# Sheet2.net
KiCad netlist of a schematic drawn in Altium Designer
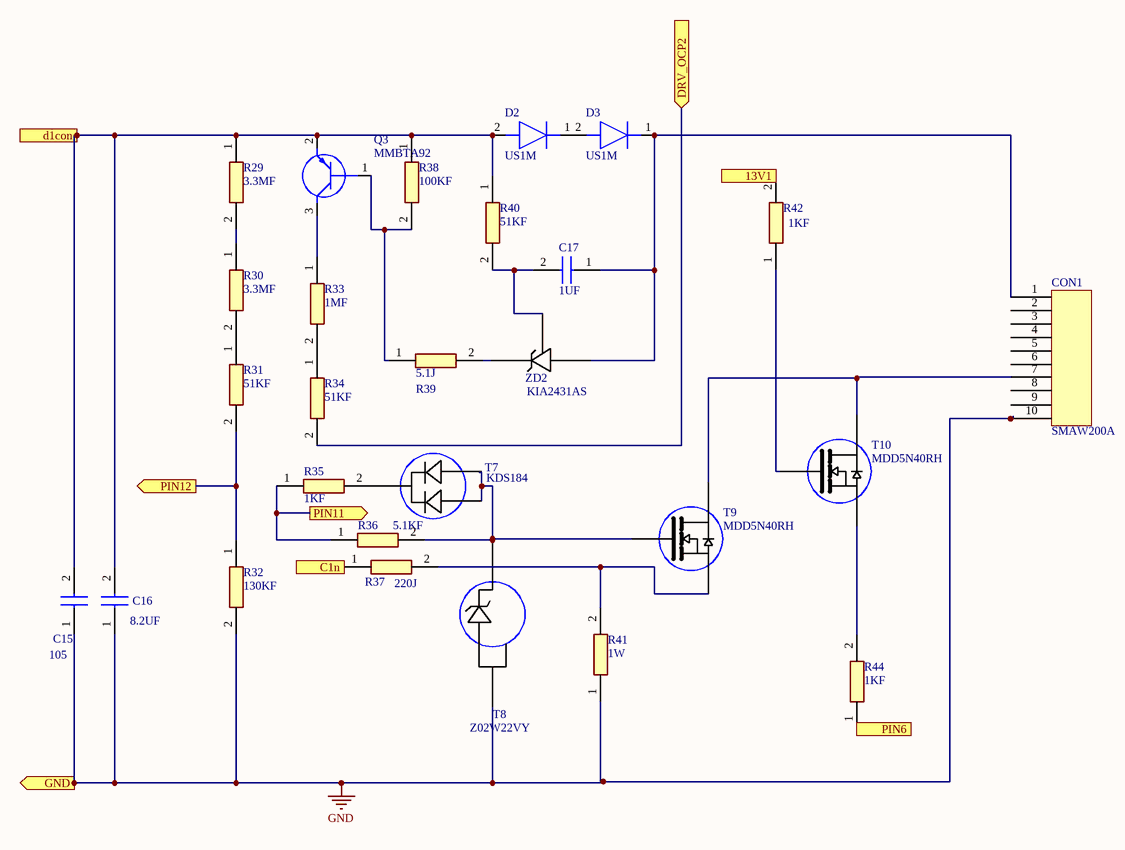
[diagram p0: Sheet2.SchDoc]

(export (version "E")
  (design (tool "Eeschema 10.0.6"))
  (components
    (comp (ref "C15")
      (value "105")
      (footprint "SamacSys:CAPPRD200W55D525H1200")
      (description "Capacitor")
      (fields
        (field (name "MANUFACTURER_PART_NUMBER") "ECA-1HM0R1")
        (field (name "MOUSER PART NUMBER") "667-ECA-1HM0R1")
      )
      (libsource (lib "*") (part "ECA-1HM0R1"))
    )
    (comp (ref "C16")
      (value "8.2UF")
      (footprint "SamacSys:CAPPRD200W55D525H1200")
      (description "Capacitor")
      (fields
        (field (name "MANUFACTURER_PART_NUMBER") "ECA-1HM0R1")
        (field (name "MOUSER PART NUMBER") "667-ECA-1HM0R1")
      )
      (libsource (lib "*") (part "ECA-1HM0R1"))
    )
    (comp (ref "C17")
      (value "1UF")
      (footprint "SamacSys:CAPPRD200W55D525H1200")
      (description "Capacitor")
      (fields
        (field (name "MANUFACTURER_PART_NUMBER") "ECA-1HM0R1")
        (field (name "MOUSER PART NUMBER") "667-ECA-1HM0R1")
      )
      (libsource (lib "*") (part "ECA-1HM0R1"))
    )
    (comp (ref "CON1")
      (value "SMAW200A")
      (footprint "SMAW200A")
      (libsource (lib "SMAW200A") (part "SMAW200A"))
    )
    (comp (ref "D2")
      (value "US1M")
      (footprint "SamacSys:DIOM5127X229N")
      (description "Diode")
      (fields
        (field (name "MANUFACTURER_PART_NUMBER") "US1M-E3/61T")
        (field (name "MOUSER PART NUMBER") "625-US1M-E3")
      )
      (libsource (lib "*") (part "US1M-E3_61T"))
    )
    (comp (ref "D3")
      (value "US1M")
      (footprint "SamacSys:DIOM5127X229N")
      (description "Diode")
      (fields
        (field (name "MANUFACTURER_PART_NUMBER") "US1M-E3/61T")
        (field (name "MOUSER PART NUMBER") "625-US1M-E3")
      )
      (libsource (lib "*") (part "US1M-E3_61T"))
    )
    (comp (ref "Q3")
      (value "MMBTA92")
      (footprint "SamacSys:SOT95P245X130-3N")
      (description "Transistor BJT PNP")
      (libsource (lib "*") (part "MMBTA92"))
    )
    (comp (ref "R29")
      (value "3.3MF")
      (footprint "SamacSys:RESAD1170W45L370D200")
      (description "Resistor")
      (fields
        (field (name "MANUFACTURER_PART_NUMBER") "MFR3-10KFC")
        (field (name "MOUSER PART NUMBER") "756-MFR3-10KFC")
      )
      (libsource (lib "*") (part "MFR3-10KFC"))
    )
    (comp (ref "R30")
      (value "3.3MF")
      (footprint "SamacSys:RESAD1170W45L370D200")
      (description "Resistor")
      (fields
        (field (name "MANUFACTURER_PART_NUMBER") "MFR3-10KFC")
        (field (name "MOUSER PART NUMBER") "756-MFR3-10KFC")
      )
      (libsource (lib "*") (part "MFR3-10KFC"))
    )
    (comp (ref "R31")
      (value "51KF")
      (footprint "SamacSys:RESAD1170W45L370D200")
      (description "Resistor")
      (fields
        (field (name "MANUFACTURER_PART_NUMBER") "MFR3-10KFC")
        (field (name "MOUSER PART NUMBER") "756-MFR3-10KFC")
      )
      (libsource (lib "*") (part "MFR3-10KFC"))
    )
    (comp (ref "R32")
      (value "130KF")
      (footprint "SamacSys:RESAD1170W45L370D200")
      (description "Resistor")
      (fields
        (field (name "MANUFACTURER_PART_NUMBER") "MFR3-10KFC")
        (field (name "MOUSER PART NUMBER") "756-MFR3-10KFC")
      )
      (libsource (lib "*") (part "MFR3-10KFC"))
    )
    (comp (ref "R33")
      (value "1MF")
      (footprint "SamacSys:RESAD1170W45L370D200")
      (description "Resistor")
      (fields
        (field (name "MANUFACTURER_PART_NUMBER") "MFR3-10KFC")
        (field (name "MOUSER PART NUMBER") "756-MFR3-10KFC")
      )
      (libsource (lib "*") (part "MFR3-10KFC"))
    )
    (comp (ref "R34")
      (value "51KF")
      (footprint "SamacSys:RESAD1170W45L370D200")
      (description "Resistor")
      (fields
        (field (name "MANUFACTURER_PART_NUMBER") "MFR3-10KFC")
        (field (name "MOUSER PART NUMBER") "756-MFR3-10KFC")
      )
      (libsource (lib "*") (part "MFR3-10KFC"))
    )
    (comp (ref "R35")
      (value "1KF")
      (footprint "SamacSys:RESAD1170W45L370D200")
      (description "Resistor")
      (fields
        (field (name "MANUFACTURER_PART_NUMBER") "MFR3-10KFC")
        (field (name "MOUSER PART NUMBER") "756-MFR3-10KFC")
      )
      (libsource (lib "") (part "MFR3-10KFC_1"))
    )
    (comp (ref "R36")
      (value "5.1KF")
      (footprint "SamacSys:RESAD1170W45L370D200")
      (description "Resistor")
      (fields
        (field (name "MANUFACTURER_PART_NUMBER") "MFR3-10KFC")
        (field (name "MOUSER PART NUMBER") "756-MFR3-10KFC")
      )
      (libsource (lib "") (part "MFR3-10KFC_1"))
    )
    (comp (ref "R37")
      (value "220J")
      (footprint "SamacSys:RESAD1170W45L370D200")
      (description "Resistor")
      (fields
        (field (name "MANUFACTURER_PART_NUMBER") "MFR3-10KFC")
        (field (name "MOUSER PART NUMBER") "756-MFR3-10KFC")
      )
      (libsource (lib "") (part "MFR3-10KFC_1"))
    )
    (comp (ref "R38")
      (value "100KF")
      (footprint "SamacSys:RESAD1170W45L370D200")
      (description "Resistor")
      (fields
        (field (name "MANUFACTURER_PART_NUMBER") "MFR3-10KFC")
        (field (name "MOUSER PART NUMBER") "756-MFR3-10KFC")
      )
      (libsource (lib "*") (part "MFR3-10KFC"))
    )
    (comp (ref "R39")
      (value "5.1J")
      (footprint "SamacSys:RESAD1170W45L370D200")
      (description "Resistor")
      (fields
        (field (name "MANUFACTURER_PART_NUMBER") "MFR3-10KFC")
        (field (name "MOUSER PART NUMBER") "756-MFR3-10KFC")
      )
      (libsource (lib "") (part "MFR3-10KFC_1"))
    )
    (comp (ref "R40")
      (value "51KF")
      (footprint "SamacSys:RESAD1170W45L370D200")
      (description "Resistor")
      (fields
        (field (name "MANUFACTURER_PART_NUMBER") "MFR3-10KFC")
        (field (name "MOUSER PART NUMBER") "756-MFR3-10KFC")
      )
      (libsource (lib "*") (part "MFR3-10KFC"))
    )
    (comp (ref "R41")
      (value "1W")
      (footprint "SamacSys:RESAD1170W45L370D200")
      (description "Resistor")
      (fields
        (field (name "MANUFACTURER_PART_NUMBER") "MFR3-10KFC")
        (field (name "MOUSER PART NUMBER") "756-MFR3-10KFC")
      )
      (libsource (lib "") (part "MFR3-10KFC_2"))
    )
    (comp (ref "R42")
      (value "1KF")
      (footprint "SamacSys:RESAD1170W45L370D200")
      (description "Resistor")
      (fields
        (field (name "MANUFACTURER_PART_NUMBER") "MFR3-10KFC")
        (field (name "MOUSER PART NUMBER") "756-MFR3-10KFC")
      )
      (libsource (lib "") (part "MFR3-10KFC_2"))
    )
    (comp (ref "R44")
      (value "1KF")
      (footprint "SamacSys:RESAD1170W45L370D200")
      (description "Resistor")
      (fields
        (field (name "MANUFACTURER_PART_NUMBER") "MFR3-10KFC")
        (field (name "MOUSER PART NUMBER") "756-MFR3-10KFC")
      )
      (libsource (lib "") (part "MFR3-10KFC_2"))
    )
    (comp (ref "T7") (value "KDS184") (libsource (lib "KDS184") (part "KDS184")))
    (comp (ref "T8") (value "Z02W22VY") (libsource (lib "Z02W22VY") (part "Z02W22VY")))
    (comp (ref "T9") (value "MDD5N40RH") (libsource (lib "MDD5N40RH") (part "MDD5N40RH")))
    (comp (ref "T10") (value "MDD5N40RH") (libsource (lib "MDD5N40RH") (part "MDD5N40RH")))
    (comp (ref "ZD2")
      (value "KIA2431AS")
      (footprint "KIA2431AS")
      (libsource (lib "KIA2431AS") (part "KIA2431AS"))
    )
  )
  (nets
    (net (code "1") (name "/13V1") (class "Default")
      (node (ref "R42") (pin "2") (pinfunction "2_2") (pintype "passive"))
    )
    (net (code "2") (name "/C1n") (class "Default")
      (node (ref "R37") (pin "1") (pinfunction "1_1") (pintype "passive"))
    )
    (net (code "3") (name "/DRV_OCP2") (class "Default")
      (node (ref "R34") (pin "2") (pinfunction "2_2") (pintype "passive"))
    )
    (net (code "4") (name "/PIN6") (class "Default")
      (node (ref "R44") (pin "1") (pinfunction "1_1") (pintype "passive"))
    )
    (net (code "5") (name "/PIN11") (class "Default")
      (node (ref "R35") (pin "1") (pinfunction "1_1") (pintype "passive"))
      (node (ref "R36") (pin "1") (pinfunction "1_1") (pintype "passive"))
    )
    (net (code "6") (name "/PIN12") (class "Default")
      (node (ref "R31") (pin "2") (pinfunction "2_2") (pintype "passive"))
      (node (ref "R32") (pin "1") (pinfunction "1_1") (pintype "passive"))
    )
    (net (code "7") (name "/d1con") (class "Default")
      (node (ref "C15") (pin "2") (pinfunction "-_2") (pintype "passive"))
      (node (ref "C16") (pin "2") (pinfunction "-_2") (pintype "passive"))
      (node (ref "D2") (pin "2") (pinfunction "A_2") (pintype "passive"))
      (node (ref "Q3") (pin "2") (pinfunction "E_2") (pintype "passive"))
      (node (ref "R29") (pin "1") (pinfunction "1_1") (pintype "passive"))
      (node (ref "R38") (pin "1") (pinfunction "1_1") (pintype "passive"))
      (node (ref "R40") (pin "1") (pinfunction "1_1") (pintype "passive"))
    )
    (net (code "8") (name "GND") (class "Default")
      (node (ref "C15") (pin "1") (pinfunction "+_1") (pintype "passive"))
      (node (ref "C16") (pin "1") (pinfunction "+_1") (pintype "passive"))
      (node (ref "CON1") (pin "10") (pinfunction "78_10") (pintype "passive"))
      (node (ref "R32") (pin "2") (pinfunction "2_2") (pintype "passive"))
      (node (ref "R41") (pin "1") (pinfunction "1_1") (pintype "passive"))
      (node (ref "T8") (pin "2") (pinfunction "65_2") (pintype "passive"))
    )
    (net (code "9") (name "Net-(C17-+)") (class "Default")
      (node (ref "C17") (pin "1") (pinfunction "+_1") (pintype "passive"))
      (node (ref "CON1") (pin "1") (pinfunction "69_1") (pintype "passive"))
      (node (ref "D3") (pin "1") (pinfunction "K_1") (pintype "passive"))
      (node (ref "ZD2") (pin "2") (pinfunction "66_2") (pintype "passive"))
    )
    (net (code "10") (name "Net-(C17--)") (class "Default")
      (node (ref "C17") (pin "2") (pinfunction "-_2") (pintype "passive"))
      (node (ref "R40") (pin "2") (pinfunction "2_2") (pintype "passive"))
      (node (ref "ZD2") (pin "3") (pinfunction "3_3") (pintype "passive"))
    )
    (net (code "11") (name "Net-(CON1-75)") (class "Default")
      (node (ref "CON1") (pin "7") (pinfunction "75_7") (pintype "passive"))
      (node (ref "T10") (pin "70") (pinfunction "70_70") (pintype "passive"))
      (node (ref "T9") (pin "70") (pinfunction "70_70") (pintype "passive"))
    )
    (net (code "12") (name "Net-(D2-K)") (class "Default")
      (node (ref "D2") (pin "1") (pinfunction "K_1") (pintype "passive"))
      (node (ref "D3") (pin "2") (pinfunction "A_2") (pintype "passive"))
    )
    (net (code "13") (name "Net-(Q3-B)") (class "Default")
      (node (ref "Q3") (pin "1") (pinfunction "B_1") (pintype "passive"))
      (node (ref "R38") (pin "2") (pinfunction "2_2") (pintype "passive"))
      (node (ref "R39") (pin "1") (pinfunction "1_1") (pintype "passive"))
    )
    (net (code "14") (name "Net-(Q3-C)") (class "Default")
      (node (ref "Q3") (pin "3") (pinfunction "C_3") (pintype "passive"))
      (node (ref "R33") (pin "1") (pinfunction "1_1") (pintype "passive"))
    )
    (net (code "15") (name "Net-(R29-Pad2)") (class "Default")
      (node (ref "R29") (pin "2") (pinfunction "2_2") (pintype "passive"))
      (node (ref "R30") (pin "1") (pinfunction "1_1") (pintype "passive"))
    )
    (net (code "16") (name "Net-(R30-Pad2)") (class "Default")
      (node (ref "R30") (pin "2") (pinfunction "2_2") (pintype "passive"))
      (node (ref "R31") (pin "1") (pinfunction "1_1") (pintype "passive"))
    )
    (net (code "17") (name "Net-(R33-Pad2)") (class "Default")
      (node (ref "R33") (pin "2") (pinfunction "2_2") (pintype "passive"))
      (node (ref "R34") (pin "1") (pinfunction "1_1") (pintype "passive"))
    )
    (net (code "18") (name "Net-(R37-Pad2)") (class "Default")
      (node (ref "R37") (pin "2") (pinfunction "2_2") (pintype "passive"))
      (node (ref "R41") (pin "2") (pinfunction "2_2") (pintype "passive"))
      (node (ref "T9") (pin "71") (pinfunction "71_71") (pintype "passive"))
    )
    (net (code "19") (name "Net-(R42-Pad1)") (class "Default")
      (node (ref "R42") (pin "1") (pinfunction "1_1") (pintype "passive"))
      (node (ref "T10") (pin "72") (pinfunction "72_72") (pintype "passive"))
    )
    (net (code "20") (name "Net-(R44-Pad2)") (class "Default")
      (node (ref "R44") (pin "2") (pinfunction "2_2") (pintype "passive"))
      (node (ref "T10") (pin "71") (pinfunction "71_71") (pintype "passive"))
    )
    (net (code "21") (name "Net-(T7-26)") (class "Default")
      (node (ref "R36") (pin "2") (pinfunction "2_2") (pintype "passive"))
      (node (ref "T7") (pin "2") (pinfunction "26_2") (pintype "passive"))
      (node (ref "T8") (pin "1") (pinfunction "64_1") (pintype "passive"))
      (node (ref "T9") (pin "72") (pinfunction "72_72") (pintype "passive"))
    )
    (net (code "22") (name "Net-(T7-27)") (class "Default")
      (node (ref "R35") (pin "2") (pinfunction "2_2") (pintype "passive"))
      (node (ref "T7") (pin "3") (pinfunction "27_3") (pintype "passive"))
    )
    (net (code "23") (name "Net-(ZD2-67)") (class "Default")
      (node (ref "R39") (pin "2") (pinfunction "2_2") (pintype "passive"))
      (node (ref "ZD2") (pin "1") (pinfunction "67_1") (pintype "passive"))
    )
    (net (code "24") (name "unconnected-(CON1-70-Pad2)") (class "Default")
      (node (ref "CON1") (pin "2") (pinfunction "70_2") (pintype "passive"))
    )
    (net (code "25") (name "unconnected-(CON1-71-Pad3)") (class "Default")
      (node (ref "CON1") (pin "3") (pinfunction "71_3") (pintype "passive"))
    )
    (net (code "26") (name "unconnected-(CON1-72-Pad4)") (class "Default")
      (node (ref "CON1") (pin "4") (pinfunction "72_4") (pintype "passive"))
    )
    (net (code "27") (name "unconnected-(CON1-73-Pad5)") (class "Default")
      (node (ref "CON1") (pin "5") (pinfunction "73_5") (pintype "passive"))
    )
    (net (code "28") (name "unconnected-(CON1-74-Pad6)") (class "Default")
      (node (ref "CON1") (pin "6") (pinfunction "74_6") (pintype "passive"))
    )
    (net (code "29") (name "unconnected-(CON1-76-Pad8)") (class "Default")
      (node (ref "CON1") (pin "8") (pinfunction "76_8") (pintype "passive"))
    )
    (net (code "30") (name "unconnected-(CON1-77-Pad9)") (class "Default")
      (node (ref "CON1") (pin "9") (pinfunction "77_9") (pintype "passive"))
    )
    (net (code "31") (name "unconnected-(T7-25-Pad1)") (class "Default")
      (node (ref "T7") (pin "1") (pinfunction "25_1") (pintype "passive"))
    )
  )
)
